# Arduino_Pro_Micro_SCH.net
KiCad netlist of a schematic drawn in Altium Designer
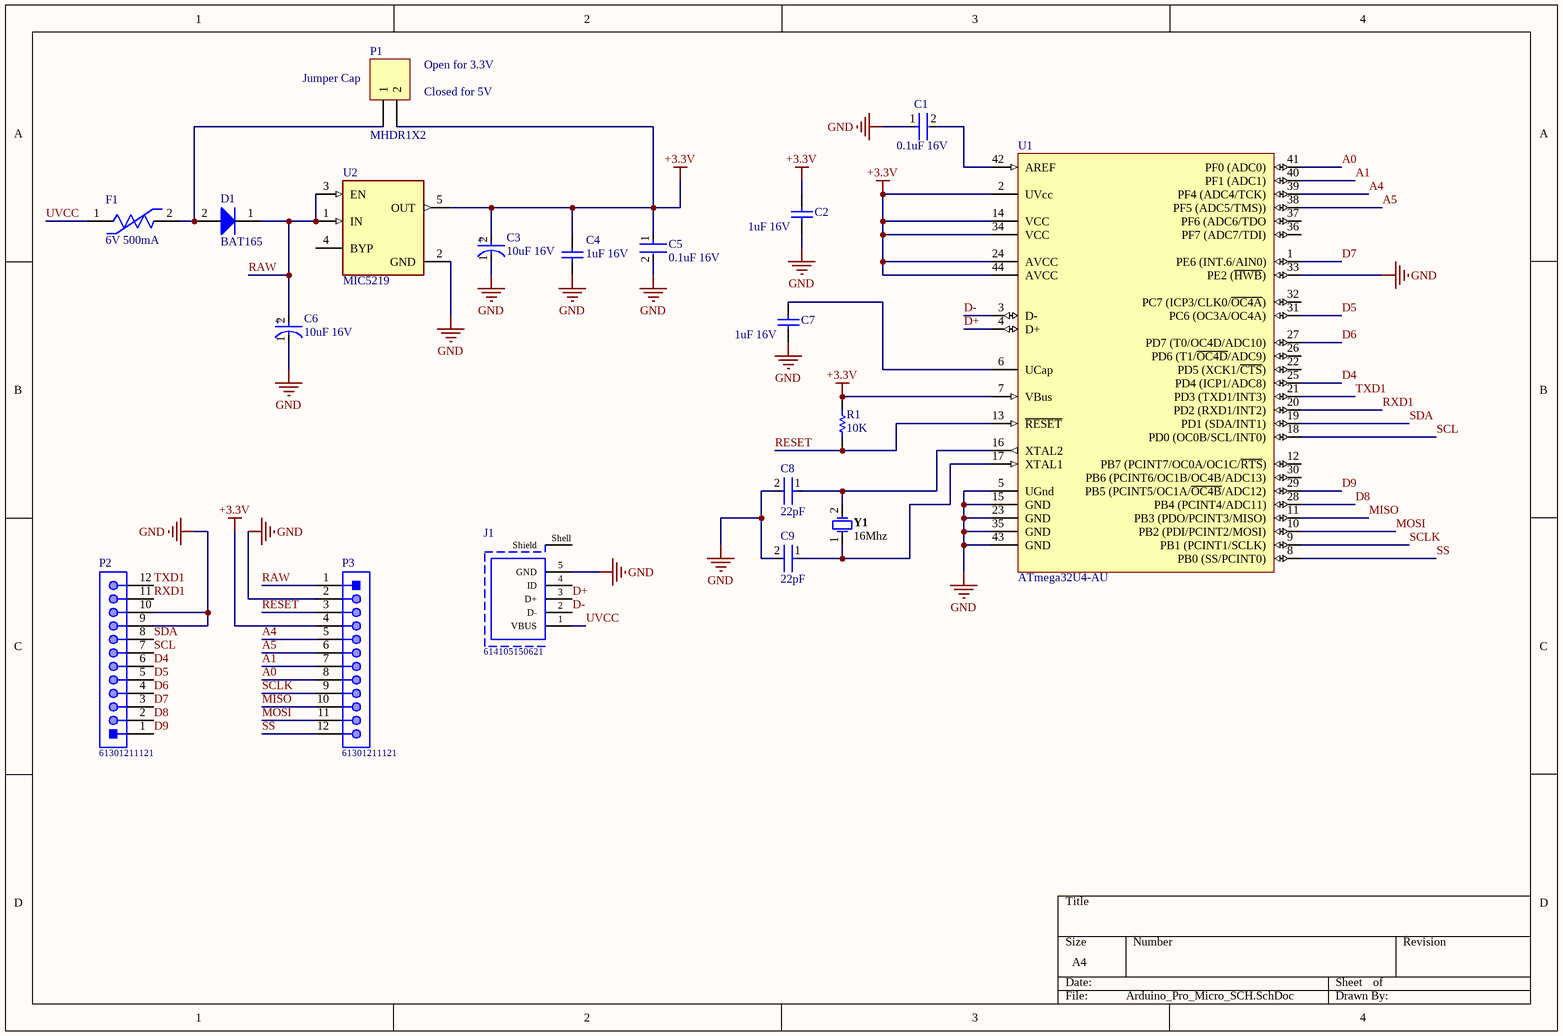
[diagram p0: Arduino_Pro_Micro_SCH.SchDoc]

(export (version "E")
  (design (tool "Eeschema 10.0.6"))
  (components
    (comp (ref "C1")
      (value "0.1uF 16V")
      (footprint "FP-C0805C-DN-MFG")
      (description "CAP CER 0.1UF 16V X7R 0805")
      (fields
        (field (name "OCTOPART") "https://octopart.com/c0805c104k4ractu-kemet-92155")
        (field (name "TOLERANCE") "0.1")
      )
      (libsource (lib "Altium Content Vault") (part "b4654b650e69147ec39a6b967a45e02"))
    )
    (comp (ref "C2")
      (value "1uF 16V")
      (footprint "CAPC2013X145X50LL20T25")
      (fields (field (name "MANUFACTURER") "Kemet") (field (name "PART NUMBER") "C0805C105K4PACTU"))
      (libsource (lib "Altium Content Vault") (part "CAP"))
    )
    (comp (ref "C3")
      (value "10uF 16V")
      (footprint "FP-T491C106K016AT-MFG")
      (description "CAP TANT 10UF 10% 16V 2312")
      (fields (field (name "VOLTAGE") "16V") (field (name "TOLERANCE") "10%"))
      (libsource (lib "Altium Content Vault") (part "a00bbbee19879c290e62620ae7e47b1"))
    )
    (comp (ref "C4")
      (value "1uF 16V")
      (footprint "CAPC2013X145X50LL20T25")
      (fields (field (name "MANUFACTURER") "Kemet") (field (name "PART NUMBER") "C0805C105K4PACTU"))
      (libsource (lib "Altium Content Vault") (part "CAP"))
    )
    (comp (ref "C5")
      (value "0.1uF 16V")
      (footprint "FP-C0805C-DN-MFG")
      (description "CAP CER 0.1UF 16V X7R 0805")
      (fields
        (field (name "OCTOPART") "https://octopart.com/c0805c104k4ractu-kemet-92155")
        (field (name "TOLERANCE") "0.1")
      )
      (libsource (lib "Altium Content Vault") (part "b4654b650e69147ec39a6b967a45e02"))
    )
    (comp (ref "C6")
      (value "10uF 16V")
      (footprint "FP-T491C106K016AT-MFG")
      (description "CAP TANT 10UF 10% 16V 2312")
      (fields (field (name "VOLTAGE") "16V") (field (name "TOLERANCE") "10%"))
      (libsource (lib "Altium Content Vault") (part "a00bbbee19879c290e62620ae7e47b1"))
    )
    (comp (ref "C7")
      (value "1uF 16V")
      (footprint "CAPC2013X145X50LL20T25")
      (fields (field (name "MANUFACTURER") "Kemet") (field (name "PART NUMBER") "C0805C105K4PACTU"))
      (libsource (lib "Altium Content Vault") (part "CAP"))
    )
    (comp (ref "C8")
      (value "22pF")
      (footprint "FP-C0805C-DN-MFG")
      (description "Capacitor; Ceramic; Cap; 22.0pF; Tol 5%; SMT; Vol-Rtg 50V; C0G; Tape and Reel")
      (fields
        (field (name "OCTOPART") "https://octopart.com/c0805c220j5gactu-kemet-145470")
        (field (name "MANUFACTURER") "KEMET")
      )
      (libsource (lib "Altium Content Vault") (part "b4654b650e69147ec39a6b967a45e02"))
    )
    (comp (ref "C9")
      (value "22pF")
      (footprint "FP-C0805C-DN-MFG")
      (description "Capacitor; Ceramic; Cap; 22.0pF; Tol 5%; SMT; Vol-Rtg 50V; C0G; Tape and Reel")
      (fields
        (field (name "OCTOPART") "https://octopart.com/c0805c220j5gactu-kemet-145470")
        (field (name "MANUFACTURER") "KEMET")
      )
      (libsource (lib "Altium Content Vault") (part "b4654b650e69147ec39a6b967a45e02"))
    )
    (comp (ref "D1")
      (value "BAT165")
      (footprint "INF-SOD323_V")
      (description "Medium Power AF Schottky Diode, SOD323, Reel, Green")
      (fields (field (name "MANUFACTURER") "Infineon"))
      (libsource (lib "Altium Content Vault") (part "INF-D_K1A2-2"))
    )
    (comp (ref "F1")
      (value "6V 500mA")
      (footprint "FP-1206L050YR-MFG")
      (description "PTC RESET FUSE 6V 500MA 1206")
      (libsource (lib "Altium Content Vault") (part "fdf083d5f6389a9a1c4e51137f46658"))
    )
    (comp (ref "J1")
      (value "614105150621")
      (footprint "614105150621")
      (description "Micro USB 2.0 Type AB Receptacle WR-COM, Vertical, THT")
      (fields (field (name "MANUFACTURER") "Wurth Elektronik") (field (name "PUBLISHER") "WurthElektronik"))
      (libsource (lib "Altium Content Vault") (part "WE-USB-5-1SHLD"))
    )
    (comp (ref "P1")
      (value "MHDR1X2")
      (footprint "MHDR1X2")
      (description "Header, 2-Pin")
      (fields (field (name "PUBLISHER") "Altium Limited"))
      (libsource (lib "Miscellaneous Connectors") (part "MHDR1X2"))
    )
    (comp (ref "P2")
      (value "61301211121")
      (footprint "61301211121")
      (description "THT Vertical Pin Header WR-PHD, Pitch 2.54 mm, Single Row, 12 pins")
      (fields (field (name "MANUFACTURER") "Wurth Elektronik") (field (name "PUBLISHER") "WurthElektronik"))
      (libsource (lib "Altium Content Vault") (part "WE-CN-1P-M-R12"))
    )
    (comp (ref "P3")
      (value "61301211121")
      (footprint "61301211121")
      (description "THT Vertical Pin Header WR-PHD, Pitch 2.54 mm, Single Row, 12 pins")
      (fields (field (name "MANUFACTURER") "Wurth Elektronik") (field (name "PUBLISHER") "WurthElektronik"))
      (libsource (lib "") (part "WE-CN-1P-M-R12_1"))
    )
    (comp (ref "R1")
      (value "10K")
      (footprint "RESC2013X60X35NL10T20")
      (description "Chip Resistor, 10 KOhm, +/- 1%, 0.125 W, -55 to 155 degC, 0805 (2012 Metric), RoHS, Tape and Reel")
      (fields (field (name "MANUFACTURER") "Yageo"))
      (libsource (lib "Altium Content Vault") (part "RES-2"))
    )
    (comp (ref "U1")
      (value "ATmega32U4-AU")
      (footprint "44ML_L")
      (libsource (lib "Altium Content Vault") (part "MC-8B-ATM16U4-SQ44"))
    )
    (comp (ref "U2")
      (value "MIC5219")
      (footprint "FP-SOT23-5LD-PL-1-IPC_C")
      (description "IC REG LINEAR 3.3V 500MA SOT23-5")
      (libsource (lib "Altium Content Vault") (part "16b36b16d6b7b40c29ab14718bc3058"))
    )
    (comp (ref "Y1")
      (value "16Mhz")
      (footprint "FOX-HC49SDLF_V")
      (description "Resistance Weld Crystal, 8 MHz, +/- 30 ppm, -20 to 70 degC, 2-Pin SMD, RoHS, Tape and Reel")
      (fields (field (name "MANUFACTURER") "FOX Electronics") (field (name "TOLERANCE") "50ppm"))
      (libsource (lib "Altium Content Vault") (part "XTAL-1-2-2"))
    )
  )
  (nets
    (net (code "1") (name "+3.3V") (class "Default")
      (node (ref "C2") (pin "2") (pinfunction "2_2") (pintype "passive"))
      (node (ref "C3") (pin "2") (pinfunction "A_2") (pintype "passive"))
      (node (ref "C4") (pin "2") (pinfunction "2_2") (pintype "passive"))
      (node (ref "C5") (pin "1") (pinfunction "1_1") (pintype "passive"))
      (node (ref "P1") (pin "2") (pinfunction "2_2") (pintype "passive"))
      (node (ref "P3") (pin "4") (pinfunction "4_4") (pintype "passive"))
      (node (ref "R1") (pin "2") (pinfunction "2_2") (pintype "passive"))
      (node (ref "U1") (pin "14") (pinfunction "VCC_14") (pintype "power_in"))
      (node (ref "U1") (pin "2") (pinfunction "UVcc_2") (pintype "power_in"))
      (node (ref "U1") (pin "24") (pinfunction "AVCC_24") (pintype "power_in"))
      (node (ref "U1") (pin "34") (pinfunction "VCC_34") (pintype "power_in"))
      (node (ref "U1") (pin "44") (pinfunction "AVCC_44") (pintype "power_in"))
      (node (ref "U1") (pin "7") (pinfunction "VBus_7") (pintype "input"))
      (node (ref "U2") (pin "5") (pinfunction "OUT_5") (pintype "output"))
    )
    (net (code "2") (name "/A0") (class "Default")
      (node (ref "P3") (pin "8") (pinfunction "8_8") (pintype "passive"))
      (node (ref "U1") (pin "41") (pinfunction "PF0_(ADC0)_41") (pintype "bidirectional"))
    )
    (net (code "3") (name "/A1") (class "Default")
      (node (ref "P3") (pin "7") (pinfunction "7_7") (pintype "passive"))
      (node (ref "U1") (pin "40") (pinfunction "PF1_(ADC1)_40") (pintype "bidirectional"))
    )
    (net (code "4") (name "/A4") (class "Default")
      (node (ref "P3") (pin "5") (pinfunction "5_5") (pintype "passive"))
      (node (ref "U1") (pin "39") (pinfunction "PF4_(ADC4/TCK)_39") (pintype "bidirectional"))
    )
    (net (code "5") (name "/A5") (class "Default")
      (node (ref "P3") (pin "6") (pinfunction "6_6") (pintype "passive"))
      (node (ref "U1") (pin "38") (pinfunction "PF5_(ADC5/TMS))_38") (pintype "bidirectional"))
    )
    (net (code "6") (name "/D+") (class "Default")
      (node (ref "J1") (pin "3") (pinfunction "D+_3") (pintype "passive"))
      (node (ref "U1") (pin "4") (pinfunction "D+_4") (pintype "bidirectional"))
    )
    (net (code "7") (name "/D-") (class "Default")
      (node (ref "J1") (pin "2") (pinfunction "D-_2") (pintype "passive"))
      (node (ref "U1") (pin "3") (pinfunction "D-_3") (pintype "bidirectional"))
    )
    (net (code "8") (name "/D4") (class "Default")
      (node (ref "P2") (pin "6") (pinfunction "6_6") (pintype "passive"))
      (node (ref "U1") (pin "25") (pinfunction "PD4_(ICP1/ADC8)_25") (pintype "bidirectional"))
    )
    (net (code "9") (name "/D5") (class "Default")
      (node (ref "P2") (pin "5") (pinfunction "5_5") (pintype "passive"))
      (node (ref "U1") (pin "31") (pinfunction "PC6_(OC3A/OC4A)_31") (pintype "bidirectional"))
    )
    (net (code "10") (name "/D6") (class "Default")
      (node (ref "P2") (pin "4") (pinfunction "4_4") (pintype "passive"))
      (node (ref "U1") (pin "27") (pinfunction "PD7_(T0/OC4D/ADC10)_27") (pintype "bidirectional"))
    )
    (net (code "11") (name "/D7") (class "Default")
      (node (ref "P2") (pin "3") (pinfunction "3_3") (pintype "passive"))
      (node (ref "U1") (pin "1") (pinfunction "PE6_(INT.6/AIN0)_1") (pintype "bidirectional"))
    )
    (net (code "12") (name "/D8") (class "Default")
      (node (ref "P2") (pin "2") (pinfunction "2_2") (pintype "passive"))
      (node (ref "U1") (pin "28") (pinfunction "PB4_(PCINT4/ADC11)_28") (pintype "bidirectional"))
    )
    (net (code "13") (name "/D9") (class "Default")
      (node (ref "P2") (pin "1") (pinfunction "1_1") (pintype "passive"))
      (node (ref "U1") (pin "29") (pinfunction "PB5_(PCINT5/OC1A/~{OC4B}/ADC12)_29") (pintype "bidirectional"))
    )
    (net (code "14") (name "/MISO") (class "Default")
      (node (ref "P3") (pin "10") (pinfunction "10_10") (pintype "passive"))
      (node (ref "U1") (pin "11") (pinfunction "PB3_(PDO/PCINT3/MISO)_11") (pintype "bidirectional"))
    )
    (net (code "15") (name "/MOSI") (class "Default")
      (node (ref "P3") (pin "11") (pinfunction "11_11") (pintype "passive"))
      (node (ref "U1") (pin "10") (pinfunction "PB2_(PDI/PCINT2/MOSI)_10") (pintype "bidirectional"))
    )
    (net (code "16") (name "/RAW") (class "Default")
      (node (ref "C6") (pin "2") (pinfunction "A_2") (pintype "passive"))
      (node (ref "D1") (pin "1") (pinfunction "K_1") (pintype "passive"))
      (node (ref "P3") (pin "1") (pinfunction "1_1") (pintype "passive"))
      (node (ref "U2") (pin "1") (pinfunction "IN_1") (pintype "input"))
      (node (ref "U2") (pin "3") (pinfunction "EN_3") (pintype "input"))
    )
    (net (code "17") (name "/RESET") (class "Default")
      (node (ref "P3") (pin "3") (pinfunction "3_3") (pintype "passive"))
      (node (ref "R1") (pin "1") (pinfunction "1_1") (pintype "passive"))
      (node (ref "U1") (pin "13") (pinfunction "~{RESET}_13") (pintype "input"))
    )
    (net (code "18") (name "/RXD1") (class "Default")
      (node (ref "P2") (pin "11") (pinfunction "11_11") (pintype "passive"))
      (node (ref "U1") (pin "20") (pinfunction "PD2_(RXD1/INT2)_20") (pintype "bidirectional"))
    )
    (net (code "19") (name "/SCL") (class "Default")
      (node (ref "P2") (pin "7") (pinfunction "7_7") (pintype "passive"))
      (node (ref "U1") (pin "18") (pinfunction "PD0_(OC0B/SCL/INT0)_18") (pintype "bidirectional"))
    )
    (net (code "20") (name "/SCLK") (class "Default")
      (node (ref "P3") (pin "9") (pinfunction "9_9") (pintype "passive"))
      (node (ref "U1") (pin "9") (pinfunction "PB1_(PCINT1/SCLK)_9") (pintype "bidirectional"))
    )
    (net (code "21") (name "/SDA") (class "Default")
      (node (ref "P2") (pin "8") (pinfunction "8_8") (pintype "passive"))
      (node (ref "U1") (pin "19") (pinfunction "PD1_(SDA/INT1)_19") (pintype "bidirectional"))
    )
    (net (code "22") (name "/SS") (class "Default")
      (node (ref "P3") (pin "12") (pinfunction "12_12") (pintype "passive"))
      (node (ref "U1") (pin "8") (pinfunction "PB0_(SS/PCINT0)_8") (pintype "bidirectional"))
    )
    (net (code "23") (name "/TXD1") (class "Default")
      (node (ref "P2") (pin "12") (pinfunction "12_12") (pintype "passive"))
      (node (ref "U1") (pin "21") (pinfunction "PD3_(TXD1/INT3)_21") (pintype "bidirectional"))
    )
    (net (code "24") (name "/UVCC") (class "Default")
      (node (ref "F1") (pin "1") (pinfunction "1_1") (pintype "passive"))
      (node (ref "J1") (pin "1") (pinfunction "VBUS_1") (pintype "passive"))
    )
    (net (code "25") (name "GND") (class "Default")
      (node (ref "C1") (pin "1") (pinfunction "1_1") (pintype "passive"))
      (node (ref "C2") (pin "1") (pinfunction "1_1") (pintype "passive"))
      (node (ref "C3") (pin "1") (pinfunction "C_1") (pintype "passive"))
      (node (ref "C4") (pin "1") (pinfunction "1_1") (pintype "passive"))
      (node (ref "C5") (pin "2") (pinfunction "2_2") (pintype "passive"))
      (node (ref "C6") (pin "1") (pinfunction "C_1") (pintype "passive"))
      (node (ref "C7") (pin "1") (pinfunction "1_1") (pintype "passive"))
      (node (ref "C8") (pin "2") (pinfunction "2_2") (pintype "passive"))
      (node (ref "C9") (pin "2") (pinfunction "2_2") (pintype "passive"))
      (node (ref "J1") (pin "5") (pinfunction "GND_5") (pintype "passive"))
      (node (ref "P2") (pin "10") (pinfunction "10_10") (pintype "passive"))
      (node (ref "P2") (pin "9") (pinfunction "9_9") (pintype "passive"))
      (node (ref "P3") (pin "2") (pinfunction "2_2") (pintype "passive"))
      (node (ref "U1") (pin "15") (pinfunction "GND_15") (pintype "power_in"))
      (node (ref "U1") (pin "23") (pinfunction "GND_23") (pintype "power_in"))
      (node (ref "U1") (pin "33") (pinfunction "PE2_(~{HWB})_33") (pintype "bidirectional"))
      (node (ref "U1") (pin "35") (pinfunction "GND_35") (pintype "power_in"))
      (node (ref "U1") (pin "43") (pinfunction "GND_43") (pintype "power_in"))
      (node (ref "U1") (pin "5") (pinfunction "UGnd_5") (pintype "power_in"))
      (node (ref "U2") (pin "2") (pinfunction "GND_2") (pintype "power_in"))
    )
    (net (code "26") (name "Net-(D1-A)") (class "Default")
      (node (ref "D1") (pin "2") (pinfunction "A_2") (pintype "passive"))
      (node (ref "F1") (pin "2") (pinfunction "2_2") (pintype "passive"))
      (node (ref "P1") (pin "1") (pinfunction "1_1") (pintype "passive"))
    )
    (net (code "27") (name "Net-(U1-AREF)") (class "Default")
      (node (ref "C1") (pin "2") (pinfunction "2_2") (pintype "passive"))
      (node (ref "U1") (pin "42") (pinfunction "AREF_42") (pintype "input"))
    )
    (net (code "28") (name "Net-(U1-UCap)") (class "Default")
      (node (ref "C7") (pin "2") (pinfunction "2_2") (pintype "passive"))
      (node (ref "U1") (pin "6") (pinfunction "UCap_6") (pintype "passive"))
    )
    (net (code "29") (name "Net-(U1-XTAL1)") (class "Default")
      (node (ref "C9") (pin "1") (pinfunction "1_1") (pintype "passive"))
      (node (ref "U1") (pin "17") (pinfunction "XTAL1_17") (pintype "input"))
      (node (ref "Y1") (pin "1") (pinfunction "1_1") (pintype "passive"))
    )
    (net (code "30") (name "Net-(U1-XTAL2)") (class "Default")
      (node (ref "C8") (pin "1") (pinfunction "1_1") (pintype "passive"))
      (node (ref "U1") (pin "16") (pinfunction "XTAL2_16") (pintype "output"))
      (node (ref "Y1") (pin "2") (pinfunction "2_2") (pintype "passive"))
    )
    (net (code "31") (name "unconnected-(J1-ID-Pad4)") (class "Default")
      (node (ref "J1") (pin "4") (pinfunction "ID_4") (pintype "passive"))
    )
    (net (code "32") (name "unconnected-(J1-Shield-PadShell)") (class "Default")
      (node (ref "J1") (pin "Shell") (pinfunction "Shield_Shell") (pintype "passive"))
    )
    (net (code "33") (name "unconnected-(U1-PB6_(PCINT6{slash}OC1B{slash}OC4B{slash}ADC13)-Pad30)") (class "Default")
      (node (ref "U1") (pin "30") (pinfunction "PB6_(PCINT6/OC1B/OC4B/ADC13)_30") (pintype "bidirectional"))
    )
    (net (code "34") (name "unconnected-(U1-PB7_(PCINT7{slash}OC0A{slash}OC1C{slash}~{RTS})-Pad12)") (class "Default")
      (node (ref "U1") (pin "12") (pinfunction "PB7_(PCINT7/OC0A/OC1C/~{RTS})_12") (pintype "bidirectional"))
    )
    (net (code "35") (name "unconnected-(U1-PC7_(ICP3{slash}CLK0{slash}~{OC4A})-Pad32)") (class "Default")
      (node (ref "U1") (pin "32") (pinfunction "PC7_(ICP3/CLK0/~{OC4A})_32") (pintype "bidirectional"))
    )
    (net (code "36") (name "unconnected-(U1-PD5_(XCK1{slash}~{CTS})-Pad22)") (class "Default")
      (node (ref "U1") (pin "22") (pinfunction "PD5_(XCK1/~{CTS})_22") (pintype "bidirectional"))
    )
    (net (code "37") (name "unconnected-(U1-PD6_(T1{slash}~{OC4D}{slash}ADC9)-Pad26)") (class "Default")
      (node (ref "U1") (pin "26") (pinfunction "PD6_(T1/~{OC4D}/ADC9)_26") (pintype "bidirectional"))
    )
    (net (code "38") (name "unconnected-(U1-PF6_(ADC6{slash}TDO-Pad37)") (class "Default")
      (node (ref "U1") (pin "37") (pinfunction "PF6_(ADC6/TDO_37") (pintype "bidirectional"))
    )
    (net (code "39") (name "unconnected-(U1-PF7_(ADC7{slash}TDI)-Pad36)") (class "Default")
      (node (ref "U1") (pin "36") (pinfunction "PF7_(ADC7/TDI)_36") (pintype "bidirectional"))
    )
    (net (code "40") (name "unconnected-(U2-BYP-Pad4)") (class "Default")
      (node (ref "U2") (pin "4") (pinfunction "BYP_4") (pintype "passive"))
    )
  )
)
